# AVALON_hashunit_power.net
KiCad netlist of a schematic drawn in Altium Designer
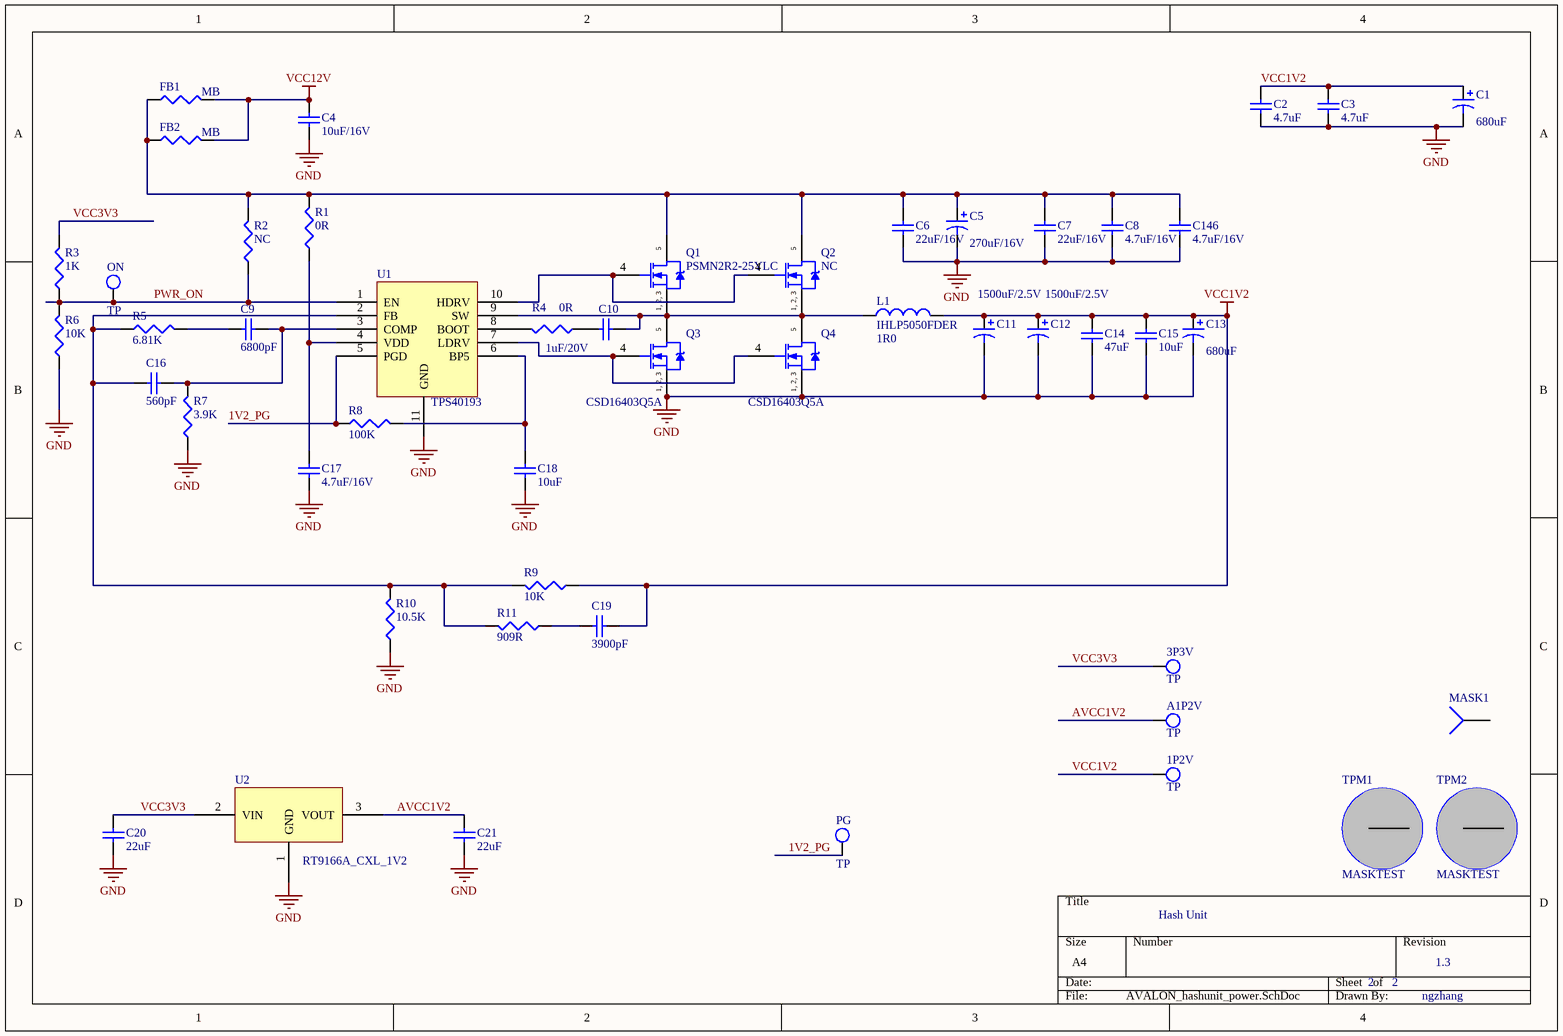
[diagram p0: AVALON_hashunit_power.SchDoc]

(export (version "E")
  (design (tool "Eeschema 10.0.6"))
  (components
    (comp (ref "1P2V") (value "TP") (footprint "TP") (libsource (lib "S6") (part "TP")))
    (comp (ref "3P3V") (value "TP") (footprint "TP") (libsource (lib "S6") (part "TP")))
    (comp (ref "A1P2V") (value "TP") (footprint "TP") (libsource (lib "S6") (part "TP")))
    (comp (ref "C1")
      (value "680uF")
      (footprint "D")
      (description "Polarized Capacitor (Surface Mount)")
      (fields (field (name "PUBLISHER") "Altium Limited"))
      (libsource (lib "Miscellaneous Devices") (part "Cap Pol3"))
    )
    (comp (ref "C2")
      (value "4.7uF")
      (footprint "CAPC1608L")
      (description "Capacitor (Semiconductor SIM Model)")
      (fields (field (name "PUBLISHER") "Altium Limited"))
      (libsource (lib "Miscellaneous Devices") (part "Cap Semi"))
    )
    (comp (ref "C3")
      (value "4.7uF")
      (footprint "CAPC1608L")
      (description "Capacitor (Semiconductor SIM Model)")
      (fields (field (name "PUBLISHER") "Altium Limited"))
      (libsource (lib "Miscellaneous Devices") (part "Cap Semi"))
    )
    (comp (ref "C4")
      (value "10uF/16V")
      (footprint "CAPC3216L")
      (description "Capacitor (Semiconductor SIM Model)")
      (fields (field (name "PUBLISHER") "Altium Limited"))
      (libsource (lib "Miscellaneous Devices") (part "Cap Semi"))
    )
    (comp (ref "C5")
      (value "270uF/16V")
      (footprint "E12")
      (description "Polarized Capacitor (Radial)")
      (fields (field (name "PUBLISHER") "Altium Limited"))
      (libsource (lib "Miscellaneous Devices") (part "Cap Pol1"))
    )
    (comp (ref "C6")
      (value "22uF/16V")
      (footprint "CAPC3225L")
      (description "Capacitor (Semiconductor SIM Model)")
      (fields (field (name "PUBLISHER") "Altium Limited"))
      (libsource (lib "Miscellaneous Devices") (part "Cap Semi"))
    )
    (comp (ref "C7")
      (value "22uF/16V")
      (footprint "CAPC3225L")
      (description "Capacitor (Semiconductor SIM Model)")
      (fields (field (name "PUBLISHER") "Altium Limited"))
      (libsource (lib "Miscellaneous Devices") (part "Cap Semi"))
    )
    (comp (ref "C8")
      (value "4.7uF/16V")
      (footprint "CAPC2012L")
      (description "Capacitor (Semiconductor SIM Model)")
      (fields (field (name "PUBLISHER") "Altium Limited"))
      (libsource (lib "Miscellaneous Devices") (part "Cap Semi"))
    )
    (comp (ref "C9")
      (value "6800pF")
      (footprint "CAPC1608L")
      (description "Capacitor (Semiconductor SIM Model)")
      (fields (field (name "PUBLISHER") "Altium Limited"))
      (libsource (lib "Miscellaneous Devices") (part "Cap Semi"))
    )
    (comp (ref "C10")
      (value "1uF/20V")
      (footprint "CAPC1608L")
      (description "Capacitor (Semiconductor SIM Model)")
      (fields (field (name "PUBLISHER") "Altium Limited"))
      (libsource (lib "Miscellaneous Devices") (part "Cap Semi"))
    )
    (comp (ref "C11")
      (value "1500uF/2.5V")
      (footprint "E12")
      (description "Polarized Capacitor (Radial)")
      (fields (field (name "PUBLISHER") "Altium Limited"))
      (libsource (lib "Miscellaneous Devices") (part "Cap Pol1"))
    )
    (comp (ref "C12")
      (value "1500uF/2.5V")
      (footprint "E12")
      (description "Polarized Capacitor (Radial)")
      (fields (field (name "PUBLISHER") "Altium Limited"))
      (libsource (lib "Miscellaneous Devices") (part "Cap Pol1"))
    )
    (comp (ref "C13")
      (value "680uF")
      (footprint "D")
      (description "Polarized Capacitor (Surface Mount)")
      (fields (field (name "PUBLISHER") "Altium Limited"))
      (libsource (lib "Miscellaneous Devices") (part "Cap Pol3"))
    )
    (comp (ref "C14")
      (value "47uF")
      (footprint "CAPC3225L")
      (description "Capacitor (Semiconductor SIM Model)")
      (fields (field (name "PUBLISHER") "Altium Limited"))
      (libsource (lib "Miscellaneous Devices") (part "Cap Semi"))
    )
    (comp (ref "C15")
      (value "10uF")
      (footprint "CAPC2012L")
      (description "Capacitor (Semiconductor SIM Model)")
      (fields (field (name "PUBLISHER") "Altium Limited"))
      (libsource (lib "Miscellaneous Devices") (part "Cap Semi"))
    )
    (comp (ref "C16")
      (value "560pF")
      (footprint "CAPC1608L")
      (description "Capacitor (Semiconductor SIM Model)")
      (fields (field (name "PUBLISHER") "Altium Limited"))
      (libsource (lib "Miscellaneous Devices") (part "Cap Semi"))
    )
    (comp (ref "C17")
      (value "4.7uF/16V")
      (footprint "CAPC2012L")
      (description "Capacitor (Semiconductor SIM Model)")
      (fields (field (name "PUBLISHER") "Altium Limited"))
      (libsource (lib "Miscellaneous Devices") (part "Cap Semi"))
    )
    (comp (ref "C18")
      (value "10uF")
      (footprint "CAPC2012L")
      (description "Capacitor (Semiconductor SIM Model)")
      (fields (field (name "PUBLISHER") "Altium Limited"))
      (libsource (lib "Miscellaneous Devices") (part "Cap Semi"))
    )
    (comp (ref "C19")
      (value "3900pF")
      (footprint "CAPC1608L")
      (description "Capacitor (Semiconductor SIM Model)")
      (fields (field (name "PUBLISHER") "Altium Limited"))
      (libsource (lib "Miscellaneous Devices") (part "Cap Semi"))
    )
    (comp (ref "C20")
      (value "22uF")
      (footprint "CAPC3216L")
      (description "Capacitor (Semiconductor SIM Model)")
      (fields (field (name "PUBLISHER") "Altium Limited"))
      (libsource (lib "Miscellaneous Devices") (part "Cap Semi"))
    )
    (comp (ref "C21")
      (value "22uF")
      (footprint "CAPC3216L")
      (description "Capacitor (Semiconductor SIM Model)")
      (fields (field (name "PUBLISHER") "Altium Limited"))
      (libsource (lib "Miscellaneous Devices") (part "Cap Semi"))
    )
    (comp (ref "C146")
      (value "4.7uF/16V")
      (footprint "CAPC2012L")
      (description "Capacitor (Semiconductor SIM Model)")
      (fields (field (name "PUBLISHER") "Altium Limited"))
      (libsource (lib "Miscellaneous Devices") (part "Cap Semi"))
    )
    (comp (ref "FB1")
      (value "MB")
      (footprint "INDC3216L")
      (description "Resistor")
      (fields (field (name "PUBLISHER") "Altium Limited"))
      (libsource (lib "Miscellaneous Devices") (part "Res3"))
    )
    (comp (ref "FB2")
      (value "MB")
      (footprint "INDC3216L")
      (description "Resistor")
      (fields (field (name "PUBLISHER") "Altium Limited"))
      (libsource (lib "Miscellaneous Devices") (part "Res3"))
    )
    (comp (ref "L1")
      (value "IHLP5050FDER")
      (footprint "IHLP5050")
      (description "Inductor")
      (fields (field (name "ALTIUM_VALUE") "1R0") (field (name "PUBLISHER") "Altium Limited"))
      (libsource (lib "Miscellaneous Devices") (part "Inductor"))
    )
    (comp (ref "MASK1")
      (value "Socket")
      (footprint "MASK_LT")
      (fields (field (name "PUBLISHER") "Altium Limited"))
      (libsource (lib "Miscellaneous Connectors") (part "Socket"))
    )
    (comp (ref "ON") (value "TP") (footprint "TP") (libsource (lib "S6") (part "TP")))
    (comp (ref "PG") (value "TP") (footprint "TP") (libsource (lib "S6") (part "TP")))
    (comp (ref "Q1") (value "PSMN2R2-25YLC") (footprint "LFPAK") (libsource (lib "S6") (part "HAT216X")))
    (comp (ref "Q2") (value "NC") (footprint "LFPAK") (libsource (lib "S6") (part "HAT216X")))
    (comp (ref "Q3") (value "CSD16403Q5A") (footprint "LFPAK") (libsource (lib "S6") (part "HAT216X")))
    (comp (ref "Q4") (value "CSD16403Q5A") (footprint "LFPAK") (libsource (lib "S6") (part "HAT216X")))
    (comp (ref "R1")
      (value "0R")
      (footprint "RESC1608L")
      (description "Resistor")
      (fields (field (name "PUBLISHER") "Altium Limited"))
      (libsource (lib "Miscellaneous Devices") (part "Res3"))
    )
    (comp (ref "R2")
      (value "NC")
      (footprint "RESC1005L")
      (description "Resistor")
      (fields (field (name "PUBLISHER") "Altium Limited"))
      (libsource (lib "Miscellaneous Devices") (part "Res3"))
    )
    (comp (ref "R3")
      (value "1K")
      (footprint "RESC1005L")
      (description "Resistor")
      (fields (field (name "PUBLISHER") "Altium Limited"))
      (libsource (lib "Miscellaneous Devices") (part "Res3"))
    )
    (comp (ref "R4")
      (value "0R")
      (footprint "RESC1608L")
      (description "Resistor")
      (fields (field (name "PUBLISHER") "Altium Limited"))
      (libsource (lib "Miscellaneous Devices") (part "Res3"))
    )
    (comp (ref "R5")
      (value "6.81K")
      (footprint "RESC1608L")
      (description "Resistor")
      (fields (field (name "PUBLISHER") "Altium Limited"))
      (libsource (lib "Miscellaneous Devices") (part "Res3"))
    )
    (comp (ref "R6")
      (value "10K")
      (footprint "RESC1608L")
      (description "Resistor")
      (fields (field (name "PUBLISHER") "Altium Limited"))
      (libsource (lib "Miscellaneous Devices") (part "Res3"))
    )
    (comp (ref "R7")
      (value "3.9K")
      (footprint "RESC1608L")
      (description "Resistor")
      (fields (field (name "PUBLISHER") "Altium Limited"))
      (libsource (lib "Miscellaneous Devices") (part "Res3"))
    )
    (comp (ref "R8")
      (value "100K")
      (footprint "RESC1005L")
      (description "Resistor")
      (fields (field (name "PUBLISHER") "Altium Limited"))
      (libsource (lib "Miscellaneous Devices") (part "Res3"))
    )
    (comp (ref "R9")
      (value "10K")
      (footprint "RESC1608L")
      (description "Resistor")
      (fields (field (name "PUBLISHER") "Altium Limited"))
      (libsource (lib "Miscellaneous Devices") (part "Res3"))
    )
    (comp (ref "R10")
      (value "10.5K")
      (footprint "RESC1608L")
      (description "Resistor")
      (fields (field (name "PUBLISHER") "Altium Limited"))
      (libsource (lib "Miscellaneous Devices") (part "Res3"))
    )
    (comp (ref "R11")
      (value "909R")
      (footprint "RESC1608L")
      (description "Resistor")
      (fields (field (name "PUBLISHER") "Altium Limited"))
      (libsource (lib "Miscellaneous Devices") (part "Res3"))
    )
    (comp (ref "TPM1") (value "MASKTEST") (footprint "MASKTEST") (libsource (lib "S6_2") (part "MASKTEST")))
    (comp (ref "TPM2") (value "MASKTEST") (footprint "MASKTEST") (libsource (lib "S6_2") (part "MASKTEST")))
    (comp (ref "U1") (value "TPS40193") (footprint "SON10") (libsource (lib "S6") (part "TPS40193")))
    (comp (ref "U2")
      (value "RT9166A_CXL_1V2")
      (footprint "SOT-89_M")
      (libsource (lib "S6_2") (part "RT9166A_CXL"))
    )
  )
  (nets
    (net (code "1") (name "/1V2_PG") (class "Default")
      (node (ref "PG") (pin "1") (pinfunction "TP_1") (pintype "passive"))
      (node (ref "R8") (pin "1") (pinfunction "1_1") (pintype "passive"))
      (node (ref "U1") (pin "5") (pinfunction "PGD_5") (pintype "passive"))
    )
    (net (code "2") (name "/AVCC1V2") (class "Default")
      (node (ref "A1P2V") (pin "1") (pinfunction "TP_1") (pintype "passive"))
      (node (ref "C21") (pin "2") (pinfunction "2_2") (pintype "passive"))
      (node (ref "U2") (pin "3") (pinfunction "VOUT_3") (pintype "passive"))
    )
    (net (code "3") (name "/PWR_ON") (class "Default")
      (node (ref "ON") (pin "1") (pinfunction "TP_1") (pintype "passive"))
      (node (ref "R2") (pin "1") (pinfunction "1_1") (pintype "passive"))
      (node (ref "R3") (pin "1") (pinfunction "1_1") (pintype "passive"))
      (node (ref "R6") (pin "2") (pinfunction "2_2") (pintype "passive"))
      (node (ref "U1") (pin "1") (pinfunction "EN_1") (pintype "passive"))
    )
    (net (code "4") (name "/VCC3V3") (class "Default")
      (node (ref "3P3V") (pin "1") (pinfunction "TP_1") (pintype "passive"))
      (node (ref "C20") (pin "2") (pinfunction "2_2") (pintype "passive"))
      (node (ref "R3") (pin "2") (pinfunction "2_2") (pintype "passive"))
      (node (ref "U2") (pin "2") (pinfunction "VIN_2") (pintype "passive"))
    )
    (net (code "5") (name "GND") (class "Default")
      (node (ref "C1") (pin "2") (pinfunction "2_2") (pintype "passive"))
      (node (ref "C11") (pin "2") (pinfunction "2_2") (pintype "passive"))
      (node (ref "C12") (pin "2") (pinfunction "2_2") (pintype "passive"))
      (node (ref "C13") (pin "2") (pinfunction "2_2") (pintype "passive"))
      (node (ref "C14") (pin "1") (pinfunction "1_1") (pintype "passive"))
      (node (ref "C146") (pin "1") (pinfunction "1_1") (pintype "passive"))
      (node (ref "C15") (pin "1") (pinfunction "1_1") (pintype "passive"))
      (node (ref "C17") (pin "1") (pinfunction "1_1") (pintype "passive"))
      (node (ref "C18") (pin "2") (pinfunction "2_2") (pintype "passive"))
      (node (ref "C2") (pin "1") (pinfunction "1_1") (pintype "passive"))
      (node (ref "C20") (pin "1") (pinfunction "1_1") (pintype "passive"))
      (node (ref "C21") (pin "1") (pinfunction "1_1") (pintype "passive"))
      (node (ref "C3") (pin "1") (pinfunction "1_1") (pintype "passive"))
      (node (ref "C4") (pin "1") (pinfunction "1_1") (pintype "passive"))
      (node (ref "C5") (pin "2") (pinfunction "2_2") (pintype "passive"))
      (node (ref "C6") (pin "1") (pinfunction "1_1") (pintype "passive"))
      (node (ref "C7") (pin "1") (pinfunction "1_1") (pintype "passive"))
      (node (ref "C8") (pin "1") (pinfunction "1_1") (pintype "passive"))
      (node (ref "Q3") (pin "1") (pinfunction "S_1") (pintype "passive"))
      (node (ref "Q3") (pin "2") (pinfunction "S_2") (pintype "passive"))
      (node (ref "Q3") (pin "3") (pinfunction "S_3") (pintype "passive"))
      (node (ref "Q4") (pin "1") (pinfunction "S_1") (pintype "passive"))
      (node (ref "Q4") (pin "2") (pinfunction "S_2") (pintype "passive"))
      (node (ref "Q4") (pin "3") (pinfunction "S_3") (pintype "passive"))
      (node (ref "R10") (pin "1") (pinfunction "1_1") (pintype "passive"))
      (node (ref "R6") (pin "1") (pinfunction "1_1") (pintype "passive"))
      (node (ref "R7") (pin "1") (pinfunction "1_1") (pintype "passive"))
      (node (ref "U1") (pin "11") (pinfunction "GND_11") (pintype "passive"))
      (node (ref "U2") (pin "1") (pinfunction "GND_1") (pintype "passive"))
    )
    (net (code "6") (name "Net-(C9-Pad2)") (class "Default")
      (node (ref "C9") (pin "2") (pinfunction "2_2") (pintype "passive"))
      (node (ref "R5") (pin "2") (pinfunction "2_2") (pintype "passive"))
    )
    (net (code "7") (name "Net-(C10-Pad2)") (class "Default")
      (node (ref "C10") (pin "2") (pinfunction "2_2") (pintype "passive"))
      (node (ref "R4") (pin "1") (pinfunction "1_1") (pintype "passive"))
    )
    (net (code "8") (name "Net-(C19-Pad1)") (class "Default")
      (node (ref "C19") (pin "1") (pinfunction "1_1") (pintype "passive"))
      (node (ref "R11") (pin "1") (pinfunction "1_1") (pintype "passive"))
    )
    (net (code "9") (name "Net-(Q1-D)") (class "Default")
      (node (ref "C146") (pin "2") (pinfunction "2_2") (pintype "passive"))
      (node (ref "C5") (pin "1") (pinfunction "1_1") (pintype "passive"))
      (node (ref "C6") (pin "2") (pinfunction "2_2") (pintype "passive"))
      (node (ref "C7") (pin "2") (pinfunction "2_2") (pintype "passive"))
      (node (ref "C8") (pin "2") (pinfunction "2_2") (pintype "passive"))
      (node (ref "FB1") (pin "1") (pinfunction "1_1") (pintype "passive"))
      (node (ref "FB2") (pin "1") (pinfunction "1_1") (pintype "passive"))
      (node (ref "Q1") (pin "5") (pinfunction "D_5") (pintype "passive"))
      (node (ref "Q2") (pin "5") (pinfunction "D_5") (pintype "passive"))
      (node (ref "R1") (pin "2") (pinfunction "2_2") (pintype "passive"))
      (node (ref "R2") (pin "2") (pinfunction "2_2") (pintype "passive"))
    )
    (net (code "10") (name "Net-(Q1-G)") (class "Default")
      (node (ref "Q1") (pin "4") (pinfunction "G_4") (pintype "passive"))
      (node (ref "Q2") (pin "4") (pinfunction "G_4") (pintype "passive"))
      (node (ref "U1") (pin "10") (pinfunction "HDRV_10") (pintype "passive"))
    )
    (net (code "11") (name "Net-(Q3-D)") (class "Default")
      (node (ref "C10") (pin "1") (pinfunction "1_1") (pintype "passive"))
      (node (ref "L1") (pin "1") (pinfunction "1_1") (pintype "passive"))
      (node (ref "Q1") (pin "1") (pinfunction "S_1") (pintype "passive"))
      (node (ref "Q1") (pin "2") (pinfunction "S_2") (pintype "passive"))
      (node (ref "Q1") (pin "3") (pinfunction "S_3") (pintype "passive"))
      (node (ref "Q2") (pin "1") (pinfunction "S_1") (pintype "passive"))
      (node (ref "Q2") (pin "2") (pinfunction "S_2") (pintype "passive"))
      (node (ref "Q2") (pin "3") (pinfunction "S_3") (pintype "passive"))
      (node (ref "Q3") (pin "5") (pinfunction "D_5") (pintype "passive"))
      (node (ref "Q4") (pin "5") (pinfunction "D_5") (pintype "passive"))
      (node (ref "U1") (pin "9") (pinfunction "SW_9") (pintype "passive"))
    )
    (net (code "12") (name "Net-(Q3-G)") (class "Default")
      (node (ref "Q3") (pin "4") (pinfunction "G_4") (pintype "passive"))
      (node (ref "Q4") (pin "4") (pinfunction "G_4") (pintype "passive"))
      (node (ref "U1") (pin "7") (pinfunction "LDRV_7") (pintype "passive"))
    )
    (net (code "13") (name "Net-(U1-BOOT)") (class "Default")
      (node (ref "R4") (pin "2") (pinfunction "2_2") (pintype "passive"))
      (node (ref "U1") (pin "8") (pinfunction "BOOT_8") (pintype "passive"))
    )
    (net (code "14") (name "Net-(U1-BP5)") (class "Default")
      (node (ref "C18") (pin "1") (pinfunction "1_1") (pintype "passive"))
      (node (ref "R8") (pin "2") (pinfunction "2_2") (pintype "passive"))
      (node (ref "U1") (pin "6") (pinfunction "BP5_6") (pintype "passive"))
    )
    (net (code "15") (name "Net-(U1-COMP)") (class "Default")
      (node (ref "C16") (pin "1") (pinfunction "1_1") (pintype "passive"))
      (node (ref "C9") (pin "1") (pinfunction "1_1") (pintype "passive"))
      (node (ref "R7") (pin "2") (pinfunction "2_2") (pintype "passive"))
      (node (ref "U1") (pin "3") (pinfunction "COMP_3") (pintype "passive"))
    )
    (net (code "16") (name "Net-(U1-FB)") (class "Default")
      (node (ref "C16") (pin "2") (pinfunction "2_2") (pintype "passive"))
      (node (ref "R10") (pin "2") (pinfunction "2_2") (pintype "passive"))
      (node (ref "R11") (pin "2") (pinfunction "2_2") (pintype "passive"))
      (node (ref "R5") (pin "1") (pinfunction "1_1") (pintype "passive"))
      (node (ref "R9") (pin "2") (pinfunction "2_2") (pintype "passive"))
      (node (ref "U1") (pin "2") (pinfunction "FB_2") (pintype "passive"))
    )
    (net (code "17") (name "Net-(U1-VDD)") (class "Default")
      (node (ref "C17") (pin "2") (pinfunction "2_2") (pintype "passive"))
      (node (ref "R1") (pin "1") (pinfunction "1_1") (pintype "passive"))
      (node (ref "U1") (pin "4") (pinfunction "VDD_4") (pintype "passive"))
    )
    (net (code "18") (name "VCC1V2") (class "Default")
      (node (ref "1P2V") (pin "1") (pinfunction "TP_1") (pintype "passive"))
      (node (ref "C1") (pin "1") (pinfunction "1_1") (pintype "passive"))
      (node (ref "C11") (pin "1") (pinfunction "1_1") (pintype "passive"))
      (node (ref "C12") (pin "1") (pinfunction "1_1") (pintype "passive"))
      (node (ref "C13") (pin "1") (pinfunction "1_1") (pintype "passive"))
      (node (ref "C14") (pin "2") (pinfunction "2_2") (pintype "passive"))
      (node (ref "C15") (pin "2") (pinfunction "2_2") (pintype "passive"))
      (node (ref "C19") (pin "2") (pinfunction "2_2") (pintype "passive"))
      (node (ref "C2") (pin "2") (pinfunction "2_2") (pintype "passive"))
      (node (ref "C3") (pin "2") (pinfunction "2_2") (pintype "passive"))
      (node (ref "L1") (pin "2") (pinfunction "2_2") (pintype "passive"))
      (node (ref "R9") (pin "1") (pinfunction "1_1") (pintype "passive"))
    )
    (net (code "19") (name "VCC12V") (class "Default")
      (node (ref "C4") (pin "2") (pinfunction "2_2") (pintype "passive"))
      (node (ref "FB1") (pin "2") (pinfunction "2_2") (pintype "passive"))
      (node (ref "FB2") (pin "2") (pinfunction "2_2") (pintype "passive"))
    )
    (net (code "20") (name "unconnected-(MASK1-Pad1)") (class "Default")
      (node (ref "MASK1") (pin "1") (pinfunction "1_1") (pintype "passive"))
    )
    (net (code "21") (name "unconnected-(TPM1-MASKTEST-Pad0)") (class "Default")
      (node (ref "TPM1") (pin "0") (pinfunction "MASKTEST_0") (pintype "passive"))
    )
    (net (code "22") (name "unconnected-(TPM2-MASKTEST-Pad0)") (class "Default")
      (node (ref "TPM2") (pin "0") (pinfunction "MASKTEST_0") (pintype "passive"))
    )
  )
)
